# DRV8305-Q1.net
KiCad netlist of a schematic drawn in Altium Designer
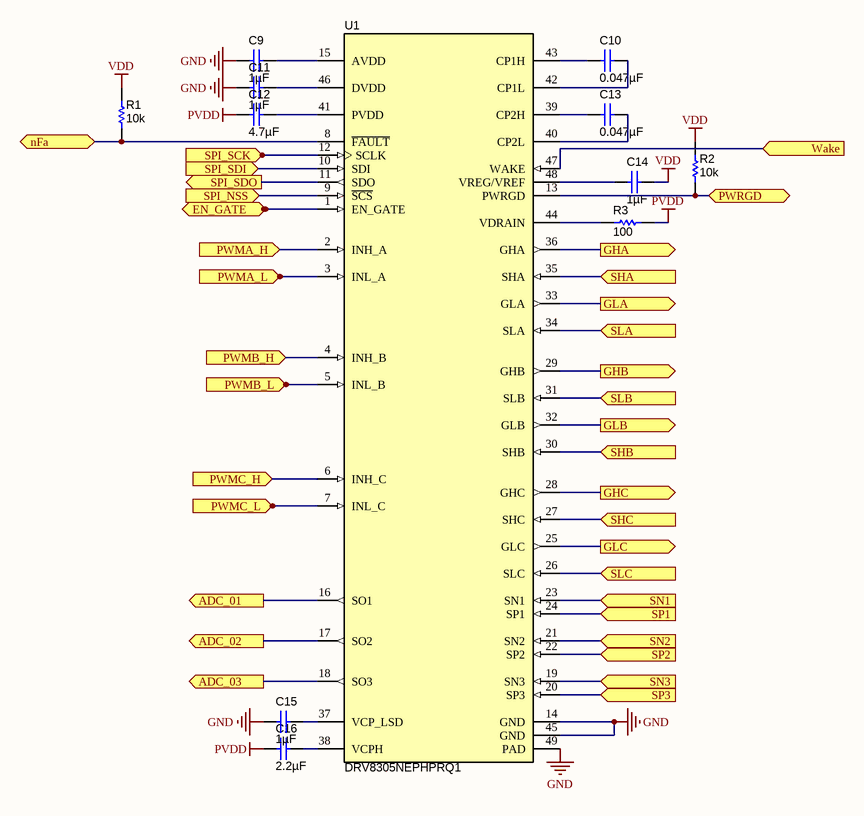
[diagram p0: DRV8305-Q1.SchDoc]

(export (version "E")
  (design (tool "Eeschema 10.0.6"))
  (components
    (comp (ref "C9")
      (value "C1608X7R1C105K")
      (footprint "0603L")
      (description "CAP, CERM, 1 µF, 16 V, +/- 10%, X7R, 0603")
      (fields
        (field (name "VALUEDISPLAYED") "1µF")
        (field (name "MANUFACTURER") "TDK")
        (field (name "PUBLISHER") "Texas Instruments")
      )
      (libsource (lib "MDBU014A") (part "C1608X7R1C105K"))
    )
    (comp (ref "C10")
      (value "C1608X7R1H473K")
      (footprint "0603L")
      (description "CAP, CERM, 0.047 µF, 50 V, +/- 10%, X7R, 0603")
      (fields
        (field (name "VALUEDISPLAYED") "0.047µF")
        (field (name "MANUFACTURER") "TDK")
        (field (name "PUBLISHER") "Texas Instruments")
      )
      (libsource (lib "MDBU014A") (part "C1608X7R1H473K"))
    )
    (comp (ref "C11")
      (value "C1608X7R1C105K")
      (footprint "0603L")
      (description "CAP, CERM, 1 µF, 16 V, +/- 10%, X7R, 0603")
      (fields
        (field (name "VALUEDISPLAYED") "1µF")
        (field (name "MANUFACTURER") "TDK")
        (field (name "PUBLISHER") "Texas Instruments")
      )
      (libsource (lib "MDBU014A") (part "C1608X7R1C105K"))
    )
    (comp (ref "C12")
      (value "GRM21BR71A475KA73L")
      (footprint "0805L")
      (description "CAP, CERM, 4.7 µF, 10 V, +/- 10%, X7R, 0805")
      (fields
        (field (name "VALUEDISPLAYED") "4.7µF")
        (field (name "MANUFACTURER") "MuRata")
        (field (name "PUBLISHER") "Texas Instruments")
      )
      (libsource (lib "MDBU014A") (part "GRM21BR71A475KA73L"))
    )
    (comp (ref "C13")
      (value "C1608X7R1H473K")
      (footprint "0603L")
      (description "CAP, CERM, 0.047 µF, 50 V, +/- 10%, X7R, 0603")
      (fields
        (field (name "VALUEDISPLAYED") "0.047µF")
        (field (name "MANUFACTURER") "TDK")
        (field (name "PUBLISHER") "Texas Instruments")
      )
      (libsource (lib "MDBU014A") (part "C1608X7R1H473K"))
    )
    (comp (ref "C14")
      (value "C1608X7R1C105K")
      (footprint "0603L")
      (description "CAP, CERM, 1 µF, 16 V, +/- 10%, X7R, 0603")
      (fields
        (field (name "VALUEDISPLAYED") "1µF")
        (field (name "MANUFACTURER") "TDK")
        (field (name "PUBLISHER") "Texas Instruments")
      )
      (libsource (lib "MDBU014A") (part "C1608X7R1C105K"))
    )
    (comp (ref "C15")
      (value "C1608X7R1C105K")
      (footprint "0603L")
      (description "CAP, CERM, 1 µF, 16 V, +/- 10%, X7R, 0603")
      (fields
        (field (name "VALUEDISPLAYED") "1µF")
        (field (name "MANUFACTURER") "TDK")
        (field (name "PUBLISHER") "Texas Instruments")
      )
      (libsource (lib "MDBU014A") (part "C1608X7R1C105K"))
    )
    (comp (ref "C16")
      (value "GRM32ER72A225KA35L")
      (footprint "1210L")
      (description "CAP, CERM, 2.2 µF, 100 V, +/- 10%, X7R, 1210")
      (fields
        (field (name "VALUEDISPLAYED") "2.2µF")
        (field (name "MANUFACTURER") "MuRata")
        (field (name "PUBLISHER") "Texas Instruments")
      )
      (libsource (lib "MDBU014A") (part "GRM32ER72A225KA35L"))
    )
    (comp (ref "R1")
      (value "10k")
      (footprint "0603L")
      (description "RES, 10 k, 5%, 0.1 W, 0603")
      (fields
        (field (name "PARTNUMBER") "CRCW060310K0JNEA")
        (field (name "MANUFACTURER") "Vishay-Dale")
        (field (name "PUBLISHER") "Texas Instruments")
      )
      (libsource (lib "MDBU014A") (part "CRCW060310K0JNEA"))
    )
    (comp (ref "R2")
      (value "10k")
      (footprint "0603L")
      (description "RES, 10 k, 5%, 0.1 W, 0603")
      (fields
        (field (name "PARTNUMBER") "CRCW060310K0JNEA")
        (field (name "MANUFACTURER") "Vishay-Dale")
        (field (name "PUBLISHER") "Texas Instruments")
      )
      (libsource (lib "MDBU014A") (part "CRCW060310K0JNEA"))
    )
    (comp (ref "R3")
      (value "100")
      (footprint "0603L")
      (description "RES, 100, 5%, 0.1 W, 0603")
      (fields
        (field (name "PARTNUMBER") "CRCW0603100RJNEA")
        (field (name "MANUFACTURER") "Vishay-Dale")
        (field (name "PUBLISHER") "Texas Instruments")
      )
      (libsource (lib "MDBU014A") (part "CRCW0603100RJNEA"))
    )
    (comp (ref "U1")
      (value "DRV8305NEPHPRQ1")
      (footprint "PHP0048G_N")
      (fields
        (field (name "ALTERNATE PARTNUMBER") "DRV8305NEPHPQ1")
        (field (name "MANUFACTURER") "Texas Instruments")
        (field (name "SYMBOLCREATOR") "Altium")
        (field (name "PUBLISHER") "Texas Instruments")
      )
      (libsource (lib "MDBU014A") (part "DRV83053EPHPRQ1"))
    )
  )
  (nets
    (net (code "1") (name "/ADC_01") (class "Default")
      (node (ref "U1") (pin "16") (pinfunction "SO1_16") (pintype "output"))
    )
    (net (code "2") (name "/ADC_02") (class "Default")
      (node (ref "U1") (pin "17") (pinfunction "SO2_17") (pintype "output"))
    )
    (net (code "3") (name "/ADC_03") (class "Default")
      (node (ref "U1") (pin "18") (pinfunction "SO3_18") (pintype "output"))
    )
    (net (code "4") (name "/EN_GATE") (class "Default")
      (node (ref "U1") (pin "1") (pinfunction "EN_GATE_1") (pintype "input"))
    )
    (net (code "5") (name "/GHA") (class "Default")
      (node (ref "U1") (pin "36") (pinfunction "GHA_36") (pintype "output"))
    )
    (net (code "6") (name "/GHB") (class "Default")
      (node (ref "U1") (pin "29") (pinfunction "GHB_29") (pintype "output"))
    )
    (net (code "7") (name "/GHC") (class "Default")
      (node (ref "U1") (pin "28") (pinfunction "GHC_28") (pintype "output"))
    )
    (net (code "8") (name "/GLA") (class "Default")
      (node (ref "U1") (pin "33") (pinfunction "GLA_33") (pintype "output"))
    )
    (net (code "9") (name "/GLB") (class "Default")
      (node (ref "U1") (pin "32") (pinfunction "GLB_32") (pintype "output"))
    )
    (net (code "10") (name "/GLC") (class "Default")
      (node (ref "U1") (pin "25") (pinfunction "GLC_25") (pintype "output"))
    )
    (net (code "11") (name "/PWMA_H") (class "Default")
      (node (ref "U1") (pin "2") (pinfunction "INH_A_2") (pintype "input"))
    )
    (net (code "12") (name "/PWMA_L") (class "Default")
      (node (ref "U1") (pin "3") (pinfunction "INL_A_3") (pintype "input"))
    )
    (net (code "13") (name "/PWMB_H") (class "Default")
      (node (ref "U1") (pin "4") (pinfunction "INH_B_4") (pintype "input"))
    )
    (net (code "14") (name "/PWMB_L") (class "Default")
      (node (ref "U1") (pin "5") (pinfunction "INL_B_5") (pintype "input"))
    )
    (net (code "15") (name "/PWMC_H") (class "Default")
      (node (ref "U1") (pin "6") (pinfunction "INH_C_6") (pintype "input"))
    )
    (net (code "16") (name "/PWMC_L") (class "Default")
      (node (ref "U1") (pin "7") (pinfunction "INL_C_7") (pintype "input"))
    )
    (net (code "17") (name "/PWRGD") (class "Default")
      (node (ref "R2") (pin "1") (pinfunction "1_1") (pintype "passive"))
      (node (ref "U1") (pin "13") (pinfunction "PWRGD_13") (pintype "open_collector"))
    )
    (net (code "18") (name "/SHA") (class "Default")
      (node (ref "U1") (pin "35") (pinfunction "SHA_35") (pintype "input"))
    )
    (net (code "19") (name "/SHB") (class "Default")
      (node (ref "U1") (pin "30") (pinfunction "SHB_30") (pintype "input"))
    )
    (net (code "20") (name "/SHC") (class "Default")
      (node (ref "U1") (pin "27") (pinfunction "SHC_27") (pintype "input"))
    )
    (net (code "21") (name "/SLA") (class "Default")
      (node (ref "U1") (pin "34") (pinfunction "SLA_34") (pintype "input"))
    )
    (net (code "22") (name "/SLB") (class "Default")
      (node (ref "U1") (pin "31") (pinfunction "SLB_31") (pintype "input"))
    )
    (net (code "23") (name "/SLC") (class "Default")
      (node (ref "U1") (pin "26") (pinfunction "SLC_26") (pintype "input"))
    )
    (net (code "24") (name "/SN1") (class "Default")
      (node (ref "U1") (pin "23") (pinfunction "SN1_23") (pintype "input"))
    )
    (net (code "25") (name "/SN2") (class "Default")
      (node (ref "U1") (pin "21") (pinfunction "SN2_21") (pintype "input"))
    )
    (net (code "26") (name "/SN3") (class "Default")
      (node (ref "U1") (pin "19") (pinfunction "SN3_19") (pintype "input"))
    )
    (net (code "27") (name "/SP1") (class "Default")
      (node (ref "U1") (pin "24") (pinfunction "SP1_24") (pintype "input"))
    )
    (net (code "28") (name "/SP2") (class "Default")
      (node (ref "U1") (pin "22") (pinfunction "SP2_22") (pintype "input"))
    )
    (net (code "29") (name "/SP3") (class "Default")
      (node (ref "U1") (pin "20") (pinfunction "SP3_20") (pintype "input"))
    )
    (net (code "30") (name "/SPI_NSS") (class "Default")
      (node (ref "U1") (pin "9") (pinfunction "SCS_9") (pintype "input"))
    )
    (net (code "31") (name "/SPI_SCK") (class "Default")
      (node (ref "U1") (pin "12") (pinfunction "SCLK_12") (pintype "input"))
    )
    (net (code "32") (name "/SPI_SDI") (class "Default")
      (node (ref "U1") (pin "10") (pinfunction "SDI_10") (pintype "input"))
    )
    (net (code "33") (name "/SPI_SDO") (class "Default")
      (node (ref "U1") (pin "11") (pinfunction "SDO_11") (pintype "output"))
    )
    (net (code "34") (name "/Wake") (class "Default")
      (node (ref "U1") (pin "47") (pinfunction "WAKE_47") (pintype "input"))
    )
    (net (code "35") (name "/nFa") (class "Default")
      (node (ref "R1") (pin "1") (pinfunction "1_1") (pintype "passive"))
      (node (ref "U1") (pin "8") (pinfunction "FAULT_8") (pintype "open_collector"))
    )
    (net (code "36") (name "GND") (class "Default")
      (node (ref "C11") (pin "2") (pinfunction "2_2") (pintype "passive"))
      (node (ref "C15") (pin "2") (pinfunction "2_2") (pintype "passive"))
      (node (ref "C9") (pin "2") (pinfunction "2_2") (pintype "passive"))
      (node (ref "U1") (pin "14") (pinfunction "GND_14") (pintype "power_in"))
      (node (ref "U1") (pin "45") (pinfunction "GND_45") (pintype "power_in"))
      (node (ref "U1") (pin "49") (pinfunction "PAD_49") (pintype "power_in"))
    )
    (net (code "37") (name "Net-(U1-AVDD)") (class "Default")
      (node (ref "C9") (pin "1") (pinfunction "1_1") (pintype "passive"))
      (node (ref "U1") (pin "15") (pinfunction "AVDD_15") (pintype "power_in"))
    )
    (net (code "38") (name "Net-(U1-CP1H)") (class "Default")
      (node (ref "C10") (pin "2") (pinfunction "2_2") (pintype "passive"))
      (node (ref "U1") (pin "43") (pinfunction "CP1H_43") (pintype "passive"))
    )
    (net (code "39") (name "Net-(U1-CP1L)") (class "Default")
      (node (ref "C10") (pin "1") (pinfunction "1_1") (pintype "passive"))
      (node (ref "U1") (pin "42") (pinfunction "CP1L_42") (pintype "passive"))
    )
    (net (code "40") (name "Net-(U1-CP2H)") (class "Default")
      (node (ref "C13") (pin "2") (pinfunction "2_2") (pintype "passive"))
      (node (ref "U1") (pin "39") (pinfunction "CP2H_39") (pintype "passive"))
    )
    (net (code "41") (name "Net-(U1-CP2L)") (class "Default")
      (node (ref "C13") (pin "1") (pinfunction "1_1") (pintype "passive"))
      (node (ref "U1") (pin "40") (pinfunction "CP2L_40") (pintype "passive"))
    )
    (net (code "42") (name "Net-(U1-DVDD)") (class "Default")
      (node (ref "C11") (pin "1") (pinfunction "1_1") (pintype "passive"))
      (node (ref "U1") (pin "46") (pinfunction "DVDD_46") (pintype "power_in"))
    )
    (net (code "43") (name "Net-(U1-PVDD)") (class "Default")
      (node (ref "C12") (pin "1") (pinfunction "1_1") (pintype "passive"))
      (node (ref "U1") (pin "41") (pinfunction "PVDD_41") (pintype "power_in"))
    )
    (net (code "44") (name "Net-(U1-VCPH)") (class "Default")
      (node (ref "C16") (pin "1") (pinfunction "1_1") (pintype "passive"))
      (node (ref "U1") (pin "38") (pinfunction "VCPH_38") (pintype "passive"))
    )
    (net (code "45") (name "Net-(U1-VCP_LSD)") (class "Default")
      (node (ref "C15") (pin "1") (pinfunction "1_1") (pintype "passive"))
      (node (ref "U1") (pin "37") (pinfunction "VCP_LSD_37") (pintype "passive"))
    )
    (net (code "46") (name "Net-(U1-VDRAIN)") (class "Default")
      (node (ref "R3") (pin "1") (pinfunction "1_1") (pintype "passive"))
      (node (ref "U1") (pin "44") (pinfunction "VDRAIN_44") (pintype "power_in"))
    )
    (net (code "47") (name "Net-(U1-VREG{slash}VREF)") (class "Default")
      (node (ref "C14") (pin "2") (pinfunction "2_2") (pintype "passive"))
      (node (ref "U1") (pin "48") (pinfunction "VREG/VREF_48") (pintype "power_in"))
    )
    (net (code "48") (name "PVDD") (class "Default")
      (node (ref "C12") (pin "2") (pinfunction "2_2") (pintype "passive"))
      (node (ref "C16") (pin "2") (pinfunction "2_2") (pintype "passive"))
      (node (ref "R3") (pin "2") (pinfunction "2_2") (pintype "passive"))
    )
    (net (code "49") (name "VDD") (class "Default")
      (node (ref "C14") (pin "1") (pinfunction "1_1") (pintype "passive"))
      (node (ref "R1") (pin "2") (pinfunction "2_2") (pintype "passive"))
      (node (ref "R2") (pin "2") (pinfunction "2_2") (pintype "passive"))
    )
  )
)
